# PowerSupply.net
KiCad netlist of a schematic drawn in Altium Designer
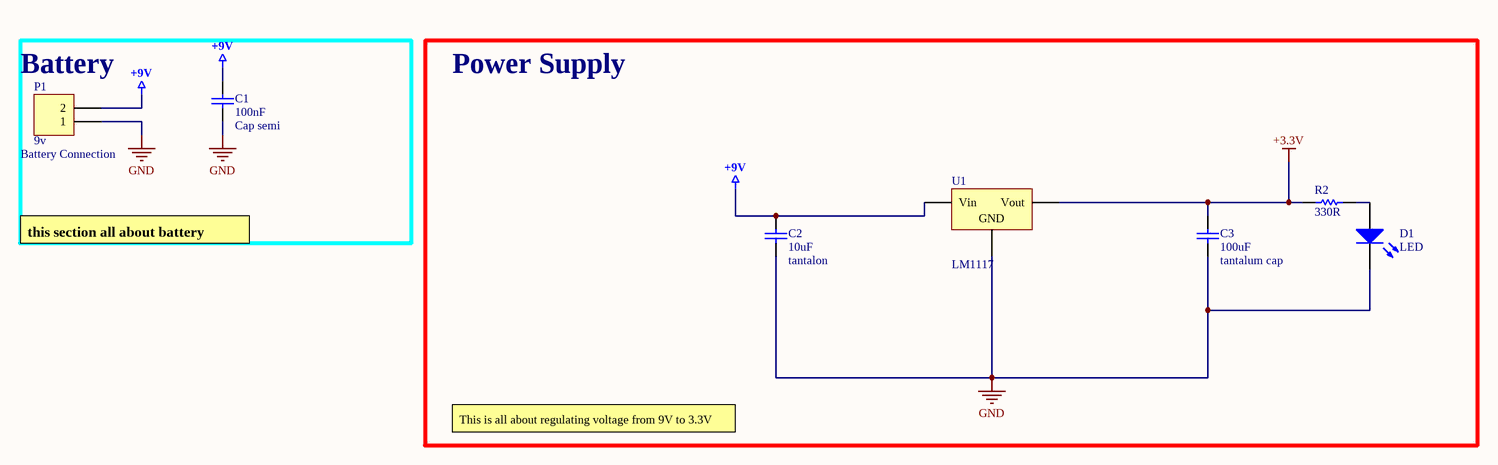
[diagram p0: PowerSupply.SchDoc]

(export (version "E")
  (design (tool "Eeschema 10.0.6"))
  (components
    (comp (ref "C1")
      (value "100nF")
      (footprint "MY_0603")
      (description "None polar capacitor")
      (fields (field (name "ASID PART NUMBER") "C-AS") (field (name "ALTIUM_UNNAMED_1") "Cap semi"))
      (libsource (lib "Mylib+Rev+4") (part "Cap ceramic"))
    )
    (comp (ref "C2")
      (value "10uF")
      (footprint "MY_0603")
      (description "None polar capacitor")
      (fields (field (name "ASID PART NUMBER") "C-AS") (field (name "ALTIUM_UNNAMED_1") "tantalon"))
      (libsource (lib "Mylib+Rev+4") (part "Cap ceramic"))
    )
    (comp (ref "C3")
      (value "100uF")
      (footprint "MY_0603")
      (description "None polar capacitor")
      (fields (field (name "ASID PART NUMBER") "C-AS") (field (name "ALTIUM_UNNAMED_1") "tantalum cap"))
      (libsource (lib "Mylib+Rev+4") (part "Cap ceramic"))
    )
    (comp (ref "D1")
      (value "LED")
      (footprint "MY_LED_0805")
      (description "Typical INFRARED GaAs LED")
      (fields (field (name "ASID PART NUMBER") "LED-AS"))
      (libsource (lib "Mylib+Rev+4") (part "LED"))
    )
    (comp (ref "P1")
      (value "Header 2")
      (footprint "My_ Power_Connector")
      (description "Header, 2-Pin")
      (fields (field (name "ASID PART NUMBER") "Header 2-AS"))
      (libsource (lib "Mylib+Rev+4") (part "Header 2"))
    )
    (comp (ref "R2")
      (value "330R")
      (footprint "MY_0805")
      (description "Standard resistor")
      (fields (field (name "ASID PART NUMBER") "Res-AS"))
      (libsource (lib "Mylib+Rev+4") (part "Res"))
    )
    (comp (ref "U1")
      (value "LM1117")
      (footprint "MY_SOT223")
      (description "Low Drop Voltage Reg")
      (fields (field (name "ASID PART NUMBER") "LM1117-AS"))
      (libsource (lib "Mylib+Rev+4") (part "LM1117"))
    )
  )
  (nets
    (net (code "1") (name "+3.3V") (class "Default")
      (node (ref "C3") (pin "2") (pinfunction "2_2") (pintype "passive"))
      (node (ref "R2") (pin "1") (pinfunction "1_1") (pintype "passive"))
      (node (ref "U1") (pin "2") (pinfunction "Vout_2") (pintype "passive"))
    )
    (net (code "2") (name "+9V") (class "Default")
      (node (ref "C1") (pin "2") (pinfunction "2_2") (pintype "passive"))
      (node (ref "C2") (pin "2") (pinfunction "2_2") (pintype "passive"))
      (node (ref "P1") (pin "2") (pinfunction "2_2") (pintype "passive"))
      (node (ref "U1") (pin "3") (pinfunction "Vin_3") (pintype "passive"))
    )
    (net (code "3") (name "GND") (class "Default")
      (node (ref "C1") (pin "1") (pinfunction "1_1") (pintype "passive"))
      (node (ref "C2") (pin "1") (pinfunction "1_1") (pintype "passive"))
      (node (ref "C3") (pin "1") (pinfunction "1_1") (pintype "passive"))
      (node (ref "D1") (pin "K") (pinfunction "K_K") (pintype "passive"))
      (node (ref "P1") (pin "1") (pinfunction "1_1") (pintype "passive"))
      (node (ref "U1") (pin "1") (pinfunction "GND_1") (pintype "passive"))
    )
    (net (code "4") (name "Net-(D1-PadA)") (class "Default")
      (node (ref "D1") (pin "A") (pinfunction "A_A") (pintype "passive"))
      (node (ref "R2") (pin "2") (pinfunction "2_2") (pintype "passive"))
    )
  )
)
